# Sheet1.net
KiCad netlist of a schematic drawn in Altium Designer
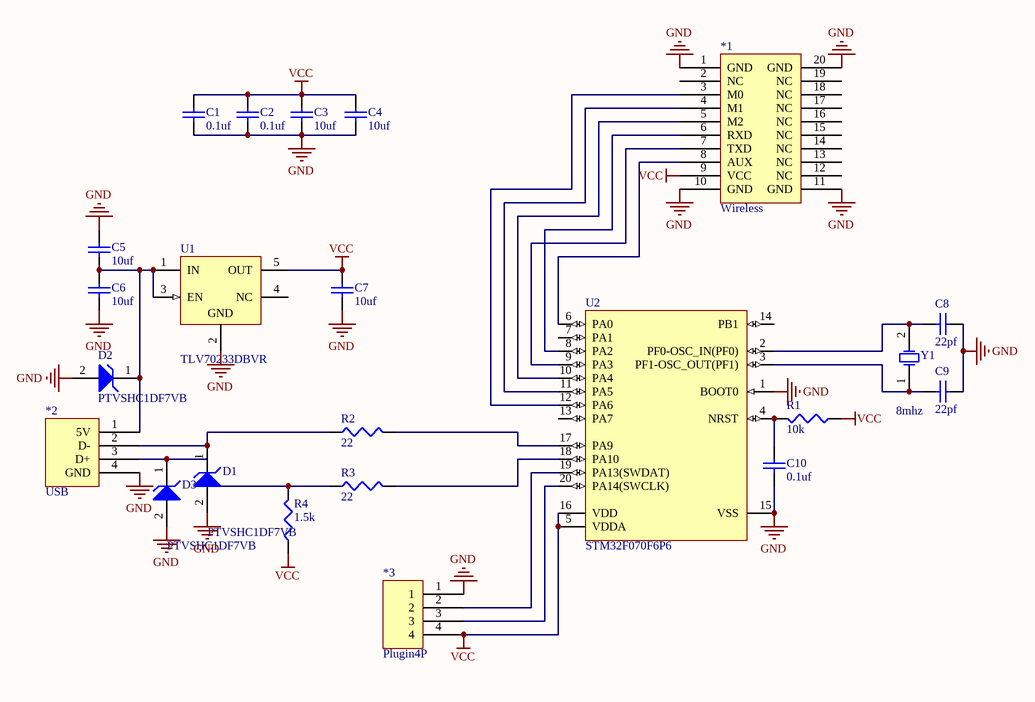
[diagram p0: Sheet1.SchDoc]

(export (version "E")
  (design (tool "Eeschema 10.0.6"))
  (components
    (comp (ref "*1") (value "Wireless") (footprint "Wireless") (libsource (lib "Schlib1") (part "Wireless")))
    (comp (ref "*2") (value "USB") (footprint "DIP10") (libsource (lib "Schlib1") (part "USB")))
    (comp (ref "*3") (value "Plugin4P") (footprint "PLUGIN4P") (libsource (lib "Schlib1") (part "Plugin4P")))
    (comp (ref "C1")
      (value "0.1uf")
      (footprint "RESC2013X65X40LL15T20")
      (description "Capacitor")
      (fields (field (name "PUBLISHER") "Altium Limited"))
      (libsource (lib "Miscellaneous Devices") (part "Cap"))
    )
    (comp (ref "C2")
      (value "0.1uf")
      (footprint "RESC2013X65X40LL15T20")
      (description "Capacitor")
      (fields (field (name "PUBLISHER") "Altium Limited"))
      (libsource (lib "Miscellaneous Devices") (part "Cap"))
    )
    (comp (ref "C3")
      (value "10uf")
      (footprint "RESC2013X65X40LL15T20")
      (description "Capacitor")
      (fields (field (name "PUBLISHER") "Altium Limited"))
      (libsource (lib "Miscellaneous Devices") (part "Cap"))
    )
    (comp (ref "C4")
      (value "10uf")
      (footprint "RESC2013X65X40LL15T20")
      (description "Capacitor")
      (fields (field (name "PUBLISHER") "Altium Limited"))
      (libsource (lib "Miscellaneous Devices") (part "Cap"))
    )
    (comp (ref "C5")
      (value "10uf")
      (footprint "RESC2013X65X40LL15T20")
      (description "Capacitor")
      (fields (field (name "PUBLISHER") "Altium Limited"))
      (libsource (lib "Miscellaneous Devices") (part "Cap"))
    )
    (comp (ref "C6")
      (value "10uf")
      (footprint "RESC2013X65X40LL15T20")
      (description "Capacitor")
      (fields (field (name "PUBLISHER") "Altium Limited"))
      (libsource (lib "Miscellaneous Devices") (part "Cap"))
    )
    (comp (ref "C7")
      (value "10uf")
      (footprint "RESC2013X65X40LL15T20")
      (description "Capacitor")
      (fields (field (name "PUBLISHER") "Altium Limited"))
      (libsource (lib "Miscellaneous Devices") (part "Cap"))
    )
    (comp (ref "C8")
      (value "22pf")
      (footprint "RESC2013X65X40LL15T20")
      (description "Capacitor")
      (fields (field (name "PUBLISHER") "Altium Limited"))
      (libsource (lib "Miscellaneous Devices") (part "Cap"))
    )
    (comp (ref "C9")
      (value "22pf")
      (footprint "RESC2013X65X40LL15T20")
      (description "Capacitor")
      (fields (field (name "PUBLISHER") "Altium Limited"))
      (libsource (lib "Miscellaneous Devices") (part "Cap"))
    )
    (comp (ref "C10")
      (value "0.1uf")
      (footprint "RESC2013X65X40LL15T20")
      (description "Capacitor")
      (fields (field (name "PUBLISHER") "Altium Limited"))
      (libsource (lib "Miscellaneous Devices") (part "Cap"))
    )
    (comp (ref "D1")
      (value "PTVSHC1DF7VB")
      (footprint "ONSC-SOD-123-2-425-04_V")
      (description "Zener Voltage Regulator, 500 mW, 2-Pin SOD-123, Pb-Free, Tape and Reel")
      (fields (field (name "MANUFACTURER") "On Semiconductor") (field (name "PARTNUMBER") "MMSZ39T1G"))
      (libsource (lib "ON Semi Zener Diodes") (part "MMSZ39T1G"))
    )
    (comp (ref "D2")
      (value "PTVSHC1DF7VB")
      (footprint "ONSC-SOD-123-2-425-04_V")
      (description "Zener Voltage Regulator, 500 mW, 2-Pin SOD-123, Pb-Free, Tape and Reel")
      (fields (field (name "MANUFACTURER") "On Semiconductor") (field (name "PARTNUMBER") "MMSZ39T1G"))
      (libsource (lib "ON Semi Zener Diodes") (part "MMSZ39T1G"))
    )
    (comp (ref "D3")
      (value "PTVSHC1DF7VB")
      (footprint "ONSC-SOD-123-2-425-04_V")
      (description "Zener Voltage Regulator, 500 mW, 2-Pin SOD-123, Pb-Free, Tape and Reel")
      (fields (field (name "MANUFACTURER") "On Semiconductor") (field (name "PARTNUMBER") "MMSZ39T1G"))
      (libsource (lib "ON Semi Zener Diodes") (part "MMSZ39T1G"))
    )
    (comp (ref "R1")
      (value "10k")
      (footprint "RESC2013X65X40LL15T20")
      (description "Resistor")
      (fields (field (name "PUBLISHER") "Altium Limited"))
      (libsource (lib "Miscellaneous Devices") (part "Res3"))
    )
    (comp (ref "R2")
      (value "22")
      (footprint "RESC2013X65X40LL15T20")
      (description "Resistor")
      (fields (field (name "PUBLISHER") "Altium Limited"))
      (libsource (lib "Miscellaneous Devices") (part "Res3"))
    )
    (comp (ref "R3")
      (value "22")
      (footprint "RESC2013X65X40LL15T20")
      (description "Resistor")
      (fields (field (name "PUBLISHER") "Altium Limited"))
      (libsource (lib "Miscellaneous Devices") (part "Res3"))
    )
    (comp (ref "R4")
      (value "1.5k")
      (footprint "RESC2013X65X40LL15T20")
      (description "Resistor")
      (fields (field (name "PUBLISHER") "Altium Limited"))
      (libsource (lib "Miscellaneous Devices") (part "Res3"))
    )
    (comp (ref "U1")
      (value "TLV70233DBVR")
      (footprint "TI-DBV5_N")
      (fields (field (name "MANUFACTURER") "Texas Instruments"))
      (libsource (lib "TI Power Management Linear Regulator Single Channel LDO (0-350mA)") (part "TLV70233DBVR"))
    )
    (comp (ref "U2")
      (value "STM32F070F6P6")
      (footprint "STM-TSSOP20_N")
      (fields (field (name "PARTNUMBER") "STM32F050F6P6"))
      (libsource (lib "STMicroelectronics STM32 F0") (part "STM32F050F6P6"))
    )
    (comp (ref "Y1")
      (value "8mhz")
      (footprint "XTAL")
      (description "Crystal Oscillator")
      (fields (field (name "PUBLISHER") "Altium Limited"))
      (libsource (lib "Miscellaneous Devices") (part "XTAL"))
    )
  )
  (nets
    (net (code "1") (name "GND") (class "Default")
      (node (ref "*1") (pin "1") (pinfunction "GND_1") (pintype "passive"))
      (node (ref "*1") (pin "10") (pinfunction "GND_10") (pintype "passive"))
      (node (ref "*1") (pin "11") (pinfunction "GND_11") (pintype "passive"))
      (node (ref "*1") (pin "20") (pinfunction "GND_20") (pintype "passive"))
      (node (ref "*2") (pin "4") (pinfunction "GND_4") (pintype "passive"))
      (node (ref "*3") (pin "1") (pinfunction "1_1") (pintype "passive"))
      (node (ref "C1") (pin "1") (pinfunction "1_1") (pintype "passive"))
      (node (ref "C10") (pin "1") (pinfunction "1_1") (pintype "passive"))
      (node (ref "C2") (pin "1") (pinfunction "1_1") (pintype "passive"))
      (node (ref "C3") (pin "1") (pinfunction "1_1") (pintype "passive"))
      (node (ref "C4") (pin "1") (pinfunction "1_1") (pintype "passive"))
      (node (ref "C5") (pin "2") (pinfunction "2_2") (pintype "passive"))
      (node (ref "C6") (pin "1") (pinfunction "1_1") (pintype "passive"))
      (node (ref "C7") (pin "1") (pinfunction "1_1") (pintype "passive"))
      (node (ref "C8") (pin "2") (pinfunction "2_2") (pintype "passive"))
      (node (ref "C9") (pin "2") (pinfunction "2_2") (pintype "passive"))
      (node (ref "D1") (pin "2") (pinfunction "A_2") (pintype "passive"))
      (node (ref "D2") (pin "2") (pinfunction "A_2") (pintype "passive"))
      (node (ref "D3") (pin "2") (pinfunction "A_2") (pintype "passive"))
      (node (ref "U1") (pin "2") (pinfunction "GND_2") (pintype "power_in"))
      (node (ref "U2") (pin "1") (pinfunction "BOOT0_1") (pintype "input"))
      (node (ref "U2") (pin "15") (pinfunction "VSS_15") (pintype "power_in"))
    )
    (net (code "2") (name "Net-(*1-AUX)") (class "Default")
      (node (ref "*1") (pin "8") (pinfunction "AUX_8") (pintype "passive"))
      (node (ref "U2") (pin "6") (pinfunction "PA0_6") (pintype "bidirectional"))
    )
    (net (code "3") (name "Net-(*1-M0)") (class "Default")
      (node (ref "*1") (pin "3") (pinfunction "M0_3") (pintype "passive"))
      (node (ref "U2") (pin "12") (pinfunction "PA6_12") (pintype "bidirectional"))
    )
    (net (code "4") (name "Net-(*1-M1)") (class "Default")
      (node (ref "*1") (pin "4") (pinfunction "M1_4") (pintype "passive"))
      (node (ref "U2") (pin "11") (pinfunction "PA5_11") (pintype "bidirectional"))
    )
    (net (code "5") (name "Net-(*1-M2)") (class "Default")
      (node (ref "*1") (pin "5") (pinfunction "M2_5") (pintype "passive"))
      (node (ref "U2") (pin "10") (pinfunction "PA4_10") (pintype "bidirectional"))
    )
    (net (code "6") (name "Net-(*1-RXD)") (class "Default")
      (node (ref "*1") (pin "6") (pinfunction "RXD_6") (pintype "passive"))
      (node (ref "U2") (pin "8") (pinfunction "PA2_8") (pintype "bidirectional"))
    )
    (net (code "7") (name "Net-(*1-TXD)") (class "Default")
      (node (ref "*1") (pin "7") (pinfunction "TXD_7") (pintype "passive"))
      (node (ref "U2") (pin "9") (pinfunction "PA3_9") (pintype "bidirectional"))
    )
    (net (code "8") (name "Net-(*2-5V)") (class "Default")
      (node (ref "*2") (pin "1") (pinfunction "5V_1") (pintype "passive"))
      (node (ref "C5") (pin "1") (pinfunction "1_1") (pintype "passive"))
      (node (ref "C6") (pin "2") (pinfunction "2_2") (pintype "passive"))
      (node (ref "D2") (pin "1") (pinfunction "K_1") (pintype "passive"))
      (node (ref "U1") (pin "1") (pinfunction "IN_1") (pintype "power_in"))
      (node (ref "U1") (pin "3") (pinfunction "EN_3") (pintype "input"))
    )
    (net (code "9") (name "Net-(*2-D+)") (class "Default")
      (node (ref "*2") (pin "3") (pinfunction "D+_3") (pintype "passive"))
      (node (ref "D3") (pin "1") (pinfunction "K_1") (pintype "passive"))
      (node (ref "R3") (pin "1") (pinfunction "1_1") (pintype "passive"))
      (node (ref "R4") (pin "2") (pinfunction "2_2") (pintype "passive"))
    )
    (net (code "10") (name "Net-(*2-D-)") (class "Default")
      (node (ref "*2") (pin "2") (pinfunction "D-_2") (pintype "passive"))
      (node (ref "D1") (pin "1") (pinfunction "K_1") (pintype "passive"))
      (node (ref "R2") (pin "1") (pinfunction "1_1") (pintype "passive"))
    )
    (net (code "11") (name "Net-(U2-NRST)") (class "Default")
      (node (ref "C10") (pin "2") (pinfunction "2_2") (pintype "passive"))
      (node (ref "R1") (pin "2") (pinfunction "2_2") (pintype "passive"))
      (node (ref "U2") (pin "4") (pinfunction "NRST_4") (pintype "bidirectional"))
    )
    (net (code "12") (name "Net-(U2-PA9)") (class "Default")
      (node (ref "R2") (pin "2") (pinfunction "2_2") (pintype "passive"))
      (node (ref "U2") (pin "17") (pinfunction "PA9_17") (pintype "bidirectional"))
    )
    (net (code "13") (name "Net-(U2-PA10)") (class "Default")
      (node (ref "R3") (pin "2") (pinfunction "2_2") (pintype "passive"))
      (node (ref "U2") (pin "18") (pinfunction "PA10_18") (pintype "bidirectional"))
    )
    (net (code "14") (name "Net-(U2-PA13(SWDAT))") (class "Default")
      (node (ref "*3") (pin "2") (pinfunction "2_2") (pintype "passive"))
      (node (ref "U2") (pin "19") (pinfunction "PA13(SWDAT)_19") (pintype "bidirectional"))
    )
    (net (code "15") (name "Net-(U2-PA14(SWCLK))") (class "Default")
      (node (ref "*3") (pin "3") (pinfunction "3_3") (pintype "passive"))
      (node (ref "U2") (pin "20") (pinfunction "PA14(SWCLK)_20") (pintype "bidirectional"))
    )
    (net (code "16") (name "Net-(U2-PF0-OSC_IN(PF0))") (class "Default")
      (node (ref "C8") (pin "1") (pinfunction "1_1") (pintype "passive"))
      (node (ref "U2") (pin "2") (pinfunction "PF0-OSC_IN(PF0)_2") (pintype "bidirectional"))
      (node (ref "Y1") (pin "2") (pinfunction "OSC2_2") (pintype "passive"))
    )
    (net (code "17") (name "Net-(U2-PF1-OSC_OUT(PF1))") (class "Default")
      (node (ref "C9") (pin "1") (pinfunction "1_1") (pintype "passive"))
      (node (ref "U2") (pin "3") (pinfunction "PF1-OSC_OUT(PF1)_3") (pintype "bidirectional"))
      (node (ref "Y1") (pin "1") (pinfunction "OSC1_1") (pintype "passive"))
    )
    (net (code "18") (name "VCC") (class "Default")
      (node (ref "*1") (pin "9") (pinfunction "VCC_9") (pintype "passive"))
      (node (ref "*3") (pin "4") (pinfunction "4_4") (pintype "passive"))
      (node (ref "C1") (pin "2") (pinfunction "2_2") (pintype "passive"))
      (node (ref "C2") (pin "2") (pinfunction "2_2") (pintype "passive"))
      (node (ref "C3") (pin "2") (pinfunction "2_2") (pintype "passive"))
      (node (ref "C4") (pin "2") (pinfunction "2_2") (pintype "passive"))
      (node (ref "C7") (pin "2") (pinfunction "2_2") (pintype "passive"))
      (node (ref "R1") (pin "1") (pinfunction "1_1") (pintype "passive"))
      (node (ref "R4") (pin "1") (pinfunction "1_1") (pintype "passive"))
      (node (ref "U1") (pin "5") (pinfunction "OUT_5") (pintype "power_in"))
      (node (ref "U2") (pin "16") (pinfunction "VDD_16") (pintype "power_in"))
      (node (ref "U2") (pin "5") (pinfunction "VDDA_5") (pintype "power_in"))
    )
    (net (code "19") (name "unconnected-(*1-NC-Pad2)") (class "Default")
      (node (ref "*1") (pin "2") (pinfunction "NC_2") (pintype "passive"))
    )
    (net (code "20") (name "unconnected-(*1-NC-Pad12)") (class "Default")
      (node (ref "*1") (pin "12") (pinfunction "NC_12") (pintype "passive"))
    )
    (net (code "21") (name "unconnected-(*1-NC-Pad13)") (class "Default")
      (node (ref "*1") (pin "13") (pinfunction "NC_13") (pintype "passive"))
    )
    (net (code "22") (name "unconnected-(*1-NC-Pad14)") (class "Default")
      (node (ref "*1") (pin "14") (pinfunction "NC_14") (pintype "passive"))
    )
    (net (code "23") (name "unconnected-(*1-NC-Pad15)") (class "Default")
      (node (ref "*1") (pin "15") (pinfunction "NC_15") (pintype "passive"))
    )
    (net (code "24") (name "unconnected-(*1-NC-Pad16)") (class "Default")
      (node (ref "*1") (pin "16") (pinfunction "NC_16") (pintype "passive"))
    )
    (net (code "25") (name "unconnected-(*1-NC-Pad17)") (class "Default")
      (node (ref "*1") (pin "17") (pinfunction "NC_17") (pintype "passive"))
    )
    (net (code "26") (name "unconnected-(*1-NC-Pad18)") (class "Default")
      (node (ref "*1") (pin "18") (pinfunction "NC_18") (pintype "passive"))
    )
    (net (code "27") (name "unconnected-(*1-NC-Pad19)") (class "Default")
      (node (ref "*1") (pin "19") (pinfunction "NC_19") (pintype "passive"))
    )
    (net (code "28") (name "unconnected-(U1-NC-Pad4)") (class "Default")
      (node (ref "U1") (pin "4") (pinfunction "NC_4") (pintype "passive"))
    )
    (net (code "29") (name "unconnected-(U2-PA1-Pad7)") (class "Default")
      (node (ref "U2") (pin "7") (pinfunction "PA1_7") (pintype "bidirectional"))
    )
    (net (code "30") (name "unconnected-(U2-PA7-Pad13)") (class "Default")
      (node (ref "U2") (pin "13") (pinfunction "PA7_13") (pintype "bidirectional"))
    )
    (net (code "31") (name "unconnected-(U2-PB1-Pad14)") (class "Default")
      (node (ref "U2") (pin "14") (pinfunction "PB1_14") (pintype "bidirectional"))
    )
  )
)
